# LCD_PCB_schemetic_1.net
KiCad netlist of a schematic drawn in Altium Designer
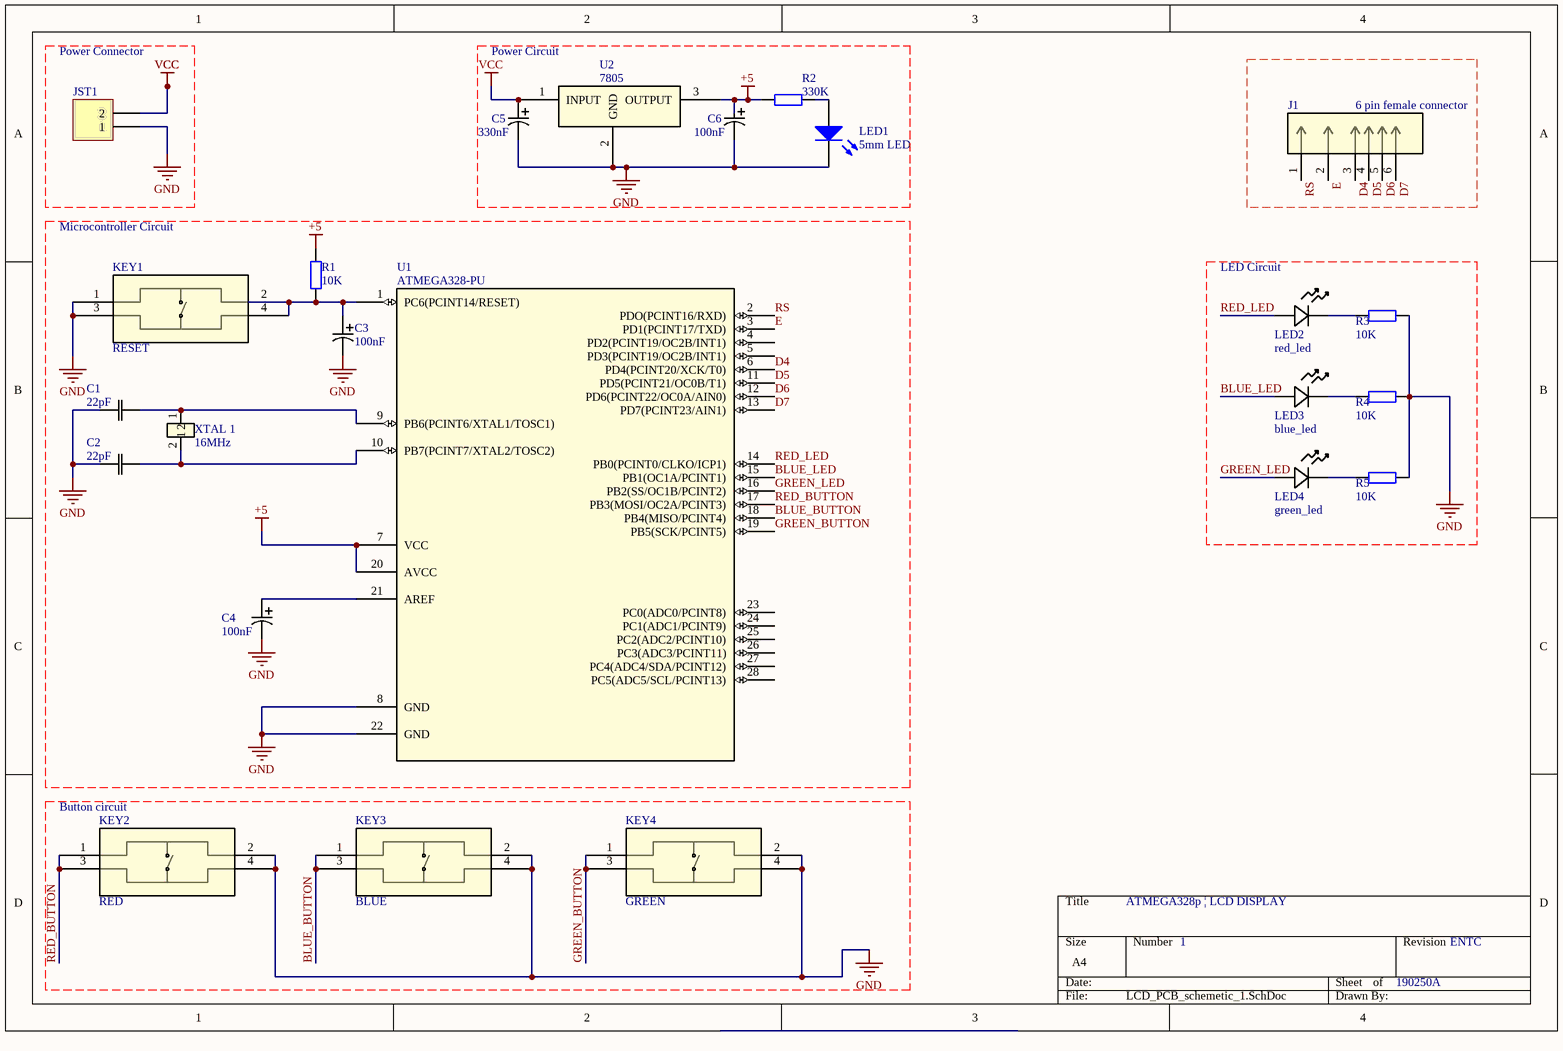
[diagram p0: LCD_PCB_schemetic_1.SchDoc]

(export (version "E")
  (design (tool "Eeschema 10.0.6"))
  (components
    (comp (ref "C1")
      (value "22pF")
      (footprint "CAP_K220J15C0GF53L2_VIS")
      (description "No Description Available")
      (fields
        (field (name "MANUFACTURER_PART_NUMBER") "K220J15C0GF53L2")
        (field (name "COPYRIGHT") "Copyright (C) 2018 Accelerated Designs. All rights reserved")
      )
      (libsource (lib "2021-05-23_06-09-59") (part "K220J15C0GF53L2"))
    )
    (comp (ref "C2")
      (value "22pF")
      (footprint "CAP_K220J15C0GF53L2_VIS")
      (description "No Description Available")
      (fields
        (field (name "MANUFACTURER_PART_NUMBER") "K220J15C0GF53L2")
        (field (name "COPYRIGHT") "Copyright (C) 2018 Accelerated Designs. All rights reserved")
      )
      (libsource (lib "2021-05-23_06-09-59") (part "K220J15C0GF53L2"))
    )
    (comp (ref "C3")
      (value "100nF")
      (footprint "PCAP_10x16_PAN")
      (description "No Description Available")
      (fields
        (field (name "MANUFACTURER_PART_NUMBER") "ECA2GM4R7")
        (field (name "COPYRIGHT") "Copyright (C) 2018 Accelerated Designs. All rights reserved")
      )
      (libsource (lib "2021-05-23_06-26-49") (part "ECA2GM4R7"))
    )
    (comp (ref "C4")
      (value "100nF")
      (footprint "PCAP_10x16_PAN")
      (description "No Description Available")
      (fields
        (field (name "MANUFACTURER_PART_NUMBER") "ECA2GM4R7")
        (field (name "COPYRIGHT") "Copyright (C) 2018 Accelerated Designs. All rights reserved")
      )
      (libsource (lib "2021-05-23_06-26-49") (part "ECA2GM4R7"))
    )
    (comp (ref "C5")
      (value "330nF")
      (footprint "PCAP_10x16_PAN")
      (description "No Description Available")
      (fields
        (field (name "MANUFACTURER_PART_NUMBER") "ECA2GM4R7")
        (field (name "COPYRIGHT") "Copyright (C) 2018 Accelerated Designs. All rights reserved")
      )
      (libsource (lib "2021-05-23_06-26-49") (part "ECA2GM4R7"))
    )
    (comp (ref "C6")
      (value "100nF")
      (footprint "PCAP_10x16_PAN")
      (description "No Description Available")
      (fields
        (field (name "MANUFACTURER_PART_NUMBER") "ECA2GM4R7")
        (field (name "COPYRIGHT") "Copyright (C) 2018 Accelerated Designs. All rights reserved")
      )
      (libsource (lib "2021-05-23_06-26-49") (part "ECA2GM4R7"))
    )
    (comp (ref "J1")
      (value "6 pin female connector")
      (footprint "CONN6_1744055-6")
      (description "3.96 EP HDR ASSY 6P VERT HT")
      (fields
        (field (name "MANUFACTURER_PART_NUMBER") "1744055-6")
        (field (name "COPYRIGHT") "Copyright (C) 2016 Accelerated Designs. All rights reserved")
      )
      (libsource (lib "2021-05-28_02-54-31") (part "1744055-6"))
    )
    (comp (ref "JST1")
      (value "~")
      (footprint "MHDR1X2")
      (description "Header, 2-Pin")
      (fields (field (name "PUBLISHER") "Altium Limited"))
      (libsource (lib "Miscellaneous Connectors") (part "MHDR1X2"))
    )
    (comp (ref "KEY1")
      (value "RESET")
      (footprint "TL1100F")
      (description "No Description Available")
      (fields
        (field (name "MANUFACTURER_PART_NUMBER") "TL1100FF160Q")
        (field (name "COPYRIGHT") "Copyright (C) 2018 Accelerated Designs. All rights reserved")
      )
      (libsource (lib "2021-05-24_16-22-31") (part "TL1100FF160Q"))
    )
    (comp (ref "KEY2")
      (value "RED")
      (footprint "TL1100F")
      (description "No Description Available")
      (fields
        (field (name "MANUFACTURER_PART_NUMBER") "TL1100FF160Q")
        (field (name "COPYRIGHT") "Copyright (C) 2018 Accelerated Designs. All rights reserved")
      )
      (libsource (lib "2021-05-24_16-22-31") (part "TL1100FF160Q"))
    )
    (comp (ref "KEY3")
      (value "BLUE")
      (footprint "TL1100F")
      (description "No Description Available")
      (fields
        (field (name "MANUFACTURER_PART_NUMBER") "TL1100FF160Q")
        (field (name "COPYRIGHT") "Copyright (C) 2018 Accelerated Designs. All rights reserved")
      )
      (libsource (lib "2021-05-24_16-22-31") (part "TL1100FF160Q"))
    )
    (comp (ref "KEY4")
      (value "GREEN")
      (footprint "TL1100F")
      (description "No Description Available")
      (fields
        (field (name "MANUFACTURER_PART_NUMBER") "TL1100FF160Q")
        (field (name "COPYRIGHT") "Copyright (C) 2018 Accelerated Designs. All rights reserved")
      )
      (libsource (lib "2021-05-24_16-22-31") (part "TL1100FF160Q"))
    )
    (comp (ref "LED1")
      (value "5mm LED")
      (footprint "LED-0")
      (description "Typical INFRARED GaAs LED")
      (fields (field (name "PUBLISHER") "Altium Limited"))
      (libsource (lib "Miscellaneous Devices") (part "LED0"))
    )
    (comp (ref "LED2")
      (value "red_led")
      (footprint "LED_SSL-LX5093BID_LUM")
      (description "No Description Available")
      (fields
        (field (name "MANUFACTURER_PART_NUMBER") "SSL-LX5093BID")
        (field (name "COPYRIGHT") "Copyright (C) 2018 Accelerated Designs. All rights reserved")
      )
      (libsource (lib "2021-05-23_09-01-29") (part "SSL-LX5093BID"))
    )
    (comp (ref "LED3")
      (value "blue_led")
      (footprint "LED_SSL-LX5093BID_LUM")
      (description "No Description Available")
      (fields
        (field (name "MANUFACTURER_PART_NUMBER") "SSL-LX5093BID")
        (field (name "COPYRIGHT") "Copyright (C) 2018 Accelerated Designs. All rights reserved")
      )
      (libsource (lib "2021-05-23_09-01-29") (part "SSL-LX5093BID"))
    )
    (comp (ref "LED4")
      (value "green_led")
      (footprint "LED_SSL-LX5093BID_LUM")
      (description "No Description Available")
      (fields
        (field (name "MANUFACTURER_PART_NUMBER") "SSL-LX5093BID")
        (field (name "COPYRIGHT") "Copyright (C) 2018 Accelerated Designs. All rights reserved")
      )
      (libsource (lib "2021-05-23_09-01-29") (part "SSL-LX5093BID"))
    )
    (comp (ref "R1")
      (value "10K")
      (footprint "AXIAL-0.4")
      (description "Resistor")
      (fields (field (name "PUBLISHER") "Altium Limited"))
      (libsource (lib "") (part "Res2_1"))
    )
    (comp (ref "R2")
      (value "330K")
      (footprint "AXIAL-0.4")
      (description "Resistor")
      (fields (field (name "PUBLISHER") "Altium Limited"))
      (libsource (lib "") (part "Res2_2"))
    )
    (comp (ref "R3")
      (value "10K")
      (footprint "AXIAL-0.4")
      (description "Resistor")
      (fields (field (name "PUBLISHER") "Altium Limited"))
      (libsource (lib "Miscellaneous Devices") (part "Res2"))
    )
    (comp (ref "R4")
      (value "10K")
      (footprint "AXIAL-0.4")
      (description "Resistor")
      (fields (field (name "PUBLISHER") "Altium Limited"))
      (libsource (lib "Miscellaneous Devices") (part "Res2"))
    )
    (comp (ref "R5")
      (value "10K")
      (footprint "AXIAL-0.4")
      (description "Resistor")
      (fields (field (name "PUBLISHER") "Altium Limited"))
      (libsource (lib "Miscellaneous Devices") (part "Res2"))
    )
    (comp (ref "U1")
      (value "ATMEGA328-PU")
      (footprint "28P3_SPDIP28_SP_MCH")
      (description "No Description Available")
      (fields (field (name "COPYRIGHT") "Copyright (C) 2018 Accelerated Designs. All rights reserved"))
      (libsource (lib "2021-05-23_04-42-26") (part "ATMEGA328-PU_1"))
    )
    (comp (ref "U2")
      (value "7805")
      (footprint "TO-220_FAS")
      (description "No Description Available")
      (fields
        (field (name "MANUFACTURER_PART_NUMBER") "LM7805CT")
        (field (name "COPYRIGHT") "Copyright (C) 2018 Accelerated Designs. All rights reserved")
      )
      (libsource (lib "2021-05-23_07-25-23") (part "LM7805CT"))
    )
    (comp (ref "XTAL 1")
      (value "16MHz")
      (footprint "SMD_ABLS_11P4X4P7_ABR")
      (description "No Description Available")
      (fields
        (field (name "MANUFACTURER_PART_NUMBER") "ABLS-16.000MHZ-B4-T")
        (field (name "COPYRIGHT") "Copyright (C) 2018 Accelerated Designs. All rights reserved")
      )
      (libsource (lib "2021-05-23_05-42-48") (part "ABLS-16.000MHZ-B4-T"))
    )
  )
  (nets
    (net (code "1") (name "+5") (class "Default")
      (node (ref "C6") (pin "1") (pinfunction "1_1") (pintype "passive"))
      (node (ref "R1") (pin "2") (pinfunction "2_2") (pintype "passive"))
      (node (ref "R2") (pin "1") (pinfunction "1_1") (pintype "passive"))
      (node (ref "U1") (pin "20") (pinfunction "AVCC_20") (pintype "power_in"))
      (node (ref "U1") (pin "7") (pinfunction "VCC_7") (pintype "power_in"))
      (node (ref "U2") (pin "3") (pinfunction "OUTPUT_3") (pintype "power_in"))
    )
    (net (code "2") (name "/BLUE_BUTTON") (class "Default")
      (node (ref "KEY3") (pin "1") (pinfunction "1_1") (pintype "passive"))
      (node (ref "KEY3") (pin "3") (pinfunction "3_3") (pintype "passive"))
      (node (ref "U1") (pin "18") (pinfunction "PB4(MISO/PCINT4)_18") (pintype "bidirectional"))
    )
    (net (code "3") (name "/BLUE_LED") (class "Default")
      (node (ref "LED3") (pin "2") (pinfunction "2_2") (pintype "passive"))
      (node (ref "U1") (pin "15") (pinfunction "PB1(OC1A/PCINT1)_15") (pintype "bidirectional"))
    )
    (net (code "4") (name "/D4") (class "Default")
      (node (ref "J1") (pin "3") (pinfunction "3_3") (pintype "passive"))
      (node (ref "U1") (pin "6") (pinfunction "PD4(PCINT20/XCK/T0)_6") (pintype "bidirectional"))
    )
    (net (code "5") (name "/D5") (class "Default")
      (node (ref "J1") (pin "4") (pinfunction "4_4") (pintype "passive"))
      (node (ref "U1") (pin "11") (pinfunction "PD5(PCINT21/OC0B/T1)_11") (pintype "bidirectional"))
    )
    (net (code "6") (name "/D6") (class "Default")
      (node (ref "J1") (pin "5") (pinfunction "5_5") (pintype "passive"))
      (node (ref "U1") (pin "12") (pinfunction "PD6(PCINT22/OC0A/AIN0)_12") (pintype "bidirectional"))
    )
    (net (code "7") (name "/D7") (class "Default")
      (node (ref "J1") (pin "6") (pinfunction "6_6") (pintype "passive"))
      (node (ref "U1") (pin "13") (pinfunction "PD7(PCINT23/AIN1)_13") (pintype "bidirectional"))
    )
    (net (code "8") (name "/E") (class "Default")
      (node (ref "J1") (pin "2") (pinfunction "2_2") (pintype "passive"))
      (node (ref "U1") (pin "3") (pinfunction "PD1(PCINT17/TXD)_3") (pintype "bidirectional"))
    )
    (net (code "9") (name "/GREEN_BUTTON") (class "Default")
      (node (ref "KEY4") (pin "1") (pinfunction "1_1") (pintype "passive"))
      (node (ref "KEY4") (pin "3") (pinfunction "3_3") (pintype "passive"))
      (node (ref "U1") (pin "19") (pinfunction "PB5(SCK/PCINT5)_19") (pintype "bidirectional"))
    )
    (net (code "10") (name "/GREEN_LED") (class "Default")
      (node (ref "LED4") (pin "2") (pinfunction "2_2") (pintype "passive"))
      (node (ref "U1") (pin "16") (pinfunction "PB2(SS/OC1B/PCINT2)_16") (pintype "bidirectional"))
    )
    (net (code "11") (name "/RED_BUTTON") (class "Default")
      (node (ref "KEY2") (pin "1") (pinfunction "1_1") (pintype "passive"))
      (node (ref "KEY2") (pin "3") (pinfunction "3_3") (pintype "passive"))
      (node (ref "U1") (pin "17") (pinfunction "PB3(MOSI/OC2A/PCINT3)_17") (pintype "bidirectional"))
    )
    (net (code "12") (name "/RED_LED") (class "Default")
      (node (ref "LED2") (pin "2") (pinfunction "2_2") (pintype "passive"))
      (node (ref "U1") (pin "14") (pinfunction "PB0(PCINT0/CLKO/ICP1)_14") (pintype "bidirectional"))
    )
    (net (code "13") (name "/RS") (class "Default")
      (node (ref "J1") (pin "1") (pinfunction "1_1") (pintype "passive"))
      (node (ref "U1") (pin "2") (pinfunction "PDO(PCINT16/RXD)_2") (pintype "bidirectional"))
    )
    (net (code "14") (name "GND") (class "Default")
      (node (ref "C1") (pin "2") (pinfunction "2_2") (pintype "passive"))
      (node (ref "C2") (pin "2") (pinfunction "2_2") (pintype "passive"))
      (node (ref "C3") (pin "2") (pinfunction "2_2") (pintype "passive"))
      (node (ref "C4") (pin "2") (pinfunction "2_2") (pintype "passive"))
      (node (ref "C5") (pin "2") (pinfunction "2_2") (pintype "passive"))
      (node (ref "C6") (pin "2") (pinfunction "2_2") (pintype "passive"))
      (node (ref "JST1") (pin "1") (pinfunction "1_1") (pintype "passive"))
      (node (ref "KEY1") (pin "1") (pinfunction "1_1") (pintype "passive"))
      (node (ref "KEY1") (pin "3") (pinfunction "3_3") (pintype "passive"))
      (node (ref "KEY2") (pin "2") (pinfunction "2_2") (pintype "passive"))
      (node (ref "KEY2") (pin "4") (pinfunction "4_4") (pintype "passive"))
      (node (ref "KEY3") (pin "2") (pinfunction "2_2") (pintype "passive"))
      (node (ref "KEY3") (pin "4") (pinfunction "4_4") (pintype "passive"))
      (node (ref "KEY4") (pin "2") (pinfunction "2_2") (pintype "passive"))
      (node (ref "KEY4") (pin "4") (pinfunction "4_4") (pintype "passive"))
      (node (ref "LED1") (pin "2") (pinfunction "K_2") (pintype "passive"))
      (node (ref "R3") (pin "1") (pinfunction "1_1") (pintype "passive"))
      (node (ref "R4") (pin "1") (pinfunction "1_1") (pintype "passive"))
      (node (ref "R5") (pin "1") (pinfunction "1_1") (pintype "passive"))
      (node (ref "U1") (pin "22") (pinfunction "GND_22") (pintype "passive"))
      (node (ref "U1") (pin "8") (pinfunction "GND_8") (pintype "passive"))
      (node (ref "U2") (pin "2") (pinfunction "GND_2") (pintype "power_in"))
    )
    (net (code "15") (name "Net-(LED1-A)") (class "Default")
      (node (ref "LED1") (pin "1") (pinfunction "A_1") (pintype "passive"))
      (node (ref "R2") (pin "2") (pinfunction "2_2") (pintype "passive"))
    )
    (net (code "16") (name "Net-(LED2-Pad1)") (class "Default")
      (node (ref "LED2") (pin "1") (pinfunction "1_1") (pintype "passive"))
      (node (ref "R3") (pin "2") (pinfunction "2_2") (pintype "passive"))
    )
    (net (code "17") (name "Net-(LED3-Pad1)") (class "Default")
      (node (ref "LED3") (pin "1") (pinfunction "1_1") (pintype "passive"))
      (node (ref "R4") (pin "2") (pinfunction "2_2") (pintype "passive"))
    )
    (net (code "18") (name "Net-(LED4-Pad1)") (class "Default")
      (node (ref "LED4") (pin "1") (pinfunction "1_1") (pintype "passive"))
      (node (ref "R5") (pin "2") (pinfunction "2_2") (pintype "passive"))
    )
    (net (code "19") (name "Net-(U1-AREF)") (class "Default")
      (node (ref "C4") (pin "1") (pinfunction "1_1") (pintype "passive"))
      (node (ref "U1") (pin "21") (pinfunction "AREF_21") (pintype "passive"))
    )
    (net (code "20") (name "Net-(U1-PB6(PCINT6{slash}XTAL1{slash}TOSC1))") (class "Default")
      (node (ref "C1") (pin "1") (pinfunction "1_1") (pintype "passive"))
      (node (ref "U1") (pin "9") (pinfunction "PB6(PCINT6/XTAL1/TOSC1)_9") (pintype "bidirectional"))
      (node (ref "XTAL 1") (pin "1") (pinfunction "1_1") (pintype "passive"))
    )
    (net (code "21") (name "Net-(U1-PB7(PCINT7{slash}XTAL2{slash}TOSC2))") (class "Default")
      (node (ref "C2") (pin "1") (pinfunction "1_1") (pintype "passive"))
      (node (ref "U1") (pin "10") (pinfunction "PB7(PCINT7/XTAL2/TOSC2)_10") (pintype "bidirectional"))
      (node (ref "XTAL 1") (pin "2") (pinfunction "2_2") (pintype "passive"))
    )
    (net (code "22") (name "Net-(U1-PC6(PCINT14{slash}RESET))") (class "Default")
      (node (ref "C3") (pin "1") (pinfunction "1_1") (pintype "passive"))
      (node (ref "KEY1") (pin "2") (pinfunction "2_2") (pintype "passive"))
      (node (ref "KEY1") (pin "4") (pinfunction "4_4") (pintype "passive"))
      (node (ref "R1") (pin "1") (pinfunction "1_1") (pintype "passive"))
      (node (ref "U1") (pin "1") (pinfunction "PC6(PCINT14/RESET)_1") (pintype "bidirectional"))
    )
    (net (code "23") (name "VCC") (class "Default")
      (node (ref "C5") (pin "1") (pinfunction "1_1") (pintype "passive"))
      (node (ref "JST1") (pin "2") (pinfunction "2_2") (pintype "passive"))
      (node (ref "U2") (pin "1") (pinfunction "INPUT_1") (pintype "power_in"))
    )
    (net (code "24") (name "unconnected-(U1-PC0(ADC0{slash}PCINT8)-Pad23)") (class "Default")
      (node (ref "U1") (pin "23") (pinfunction "PC0(ADC0/PCINT8)_23") (pintype "bidirectional"))
    )
    (net (code "25") (name "unconnected-(U1-PC1(ADC1{slash}PCINT9)-Pad24)") (class "Default")
      (node (ref "U1") (pin "24") (pinfunction "PC1(ADC1/PCINT9)_24") (pintype "bidirectional"))
    )
    (net (code "26") (name "unconnected-(U1-PC2(ADC2{slash}PCINT10)-Pad25)") (class "Default")
      (node (ref "U1") (pin "25") (pinfunction "PC2(ADC2/PCINT10)_25") (pintype "bidirectional"))
    )
    (net (code "27") (name "unconnected-(U1-PC3(ADC3{slash}PCINT11)-Pad26)") (class "Default")
      (node (ref "U1") (pin "26") (pinfunction "PC3(ADC3/PCINT11)_26") (pintype "bidirectional"))
    )
    (net (code "28") (name "unconnected-(U1-PC4(ADC4{slash}SDA{slash}PCINT12)-Pad27)") (class "Default")
      (node (ref "U1") (pin "27") (pinfunction "PC4(ADC4/SDA/PCINT12)_27") (pintype "bidirectional"))
    )
    (net (code "29") (name "unconnected-(U1-PC5(ADC5{slash}SCL{slash}PCINT13)-Pad28)") (class "Default")
      (node (ref "U1") (pin "28") (pinfunction "PC5(ADC5/SCL/PCINT13)_28") (pintype "bidirectional"))
    )
    (net (code "30") (name "unconnected-(U1-PD2(PCINT19{slash}OC2B{slash}INT1)-Pad4)") (class "Default")
      (node (ref "U1") (pin "4") (pinfunction "PD2(PCINT19/OC2B/INT1)_4") (pintype "bidirectional"))
    )
    (net (code "31") (name "unconnected-(U1-PD3(PCINT19{slash}OC2B{slash}INT1)-Pad5)") (class "Default")
      (node (ref "U1") (pin "5") (pinfunction "PD3(PCINT19/OC2B/INT1)_5") (pintype "bidirectional"))
    )
  )
)
